# current_source.net
KiCad netlist of a schematic drawn in Altium Designer
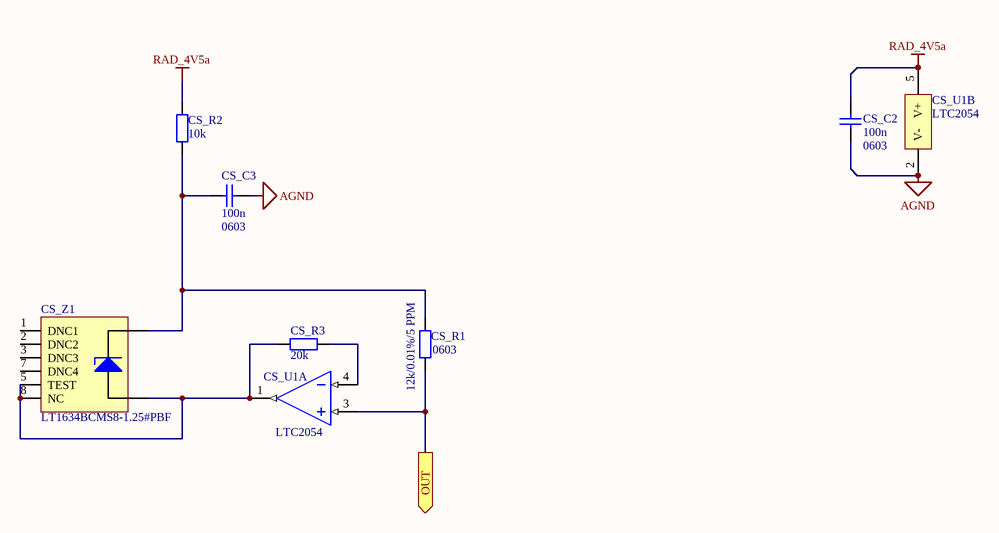
[diagram p0: current_source.SchDoc]

(export (version "E")
  (design (tool "Eeschema 10.0.6"))
  (components
    (comp (ref "CS_C2")
      (value "100n")
      (footprint "SMD_Capacitor_0603")
      (description "Cap")
      (fields (field (name "PACKAGE") "0603"))
      (libsource (lib "capacitors") (part "Cap"))
    )
    (comp (ref "CS_C3")
      (value "100n")
      (footprint "SMD_Capacitor_0603")
      (description "Cap")
      (fields (field (name "PACKAGE") "0603"))
      (libsource (lib "capacitors") (part "Cap"))
    )
    (comp (ref "CS_R1")
      (value "12k/0.01%/5 PPM")
      (footprint "SMD_Resistor_0603")
      (fields (field (name "PACKAGE") "0603"))
      (libsource (lib "") (part "Res_1"))
    )
    (comp (ref "CS_R2") (value "10k") (footprint "SMD_Resistor_0603") (libsource (lib "") (part "Res_1")))
    (comp (ref "CS_R3")
      (value "20k")
      (footprint "SMD_Resistor_0603")
      (libsource (lib "resistors") (part "Res"))
    )
    (comp (ref "CS_U1")
      (value "LTC2054")
      (footprint "SOT23-5")
      (description "Single/Dual Micropower  Zero-Drift Operational Amplifi ers")
      (fields (field (name "MANUFACTURER") "Linear Technology"))
      (libsource (lib "") (part "LTC2054_1"))
    )
    (comp (ref "CS_Z1")
      (value "1.25V")
      (footprint "MSOP-8")
      (description "Micropower Precision  Shunt Voltage Reference")
      (fields
        (field (name "MANUFACTURER") "Linear")
        (field (name "MANUFACTURERPARTNUMBER") "LT1634BCMS8-1.25#PBF")
      )
      (libsource (lib "diodes") (part "LT1634BCMS8-1.25#PBF"))
    )
  )
  (nets
    (net (code "1") (name "/OUT") (class "Default")
      (node (ref "CS_R1") (pin "2") (pinfunction "2_2") (pintype "passive"))
      (node (ref "CS_U1") (pin "3") (pinfunction "IN+_A_3") (pintype "input"))
    )
    (net (code "2") (name "AGND") (class "Default")
      (node (ref "CS_C2") (pin "2") (pinfunction "2_2") (pintype "passive"))
      (node (ref "CS_C3") (pin "1") (pinfunction "1_1") (pintype "passive"))
      (node (ref "CS_U1") (pin "2") (pinfunction "V-_2") (pintype "power_in"))
    )
    (net (code "3") (name "Net-(CS_U1A-IN-_A)") (class "Default")
      (node (ref "CS_R3") (pin "2") (pinfunction "2_2") (pintype "passive"))
      (node (ref "CS_U1") (pin "4") (pinfunction "IN-_A_4") (pintype "input"))
    )
    (net (code "4") (name "Net-(CS_U1A-OUT_A)") (class "Default")
      (node (ref "CS_R3") (pin "1") (pinfunction "1_1") (pintype "passive"))
      (node (ref "CS_U1") (pin "1") (pinfunction "OUT_A_1") (pintype "output"))
      (node (ref "CS_Z1") (pin "4") (pinfunction "A_4") (pintype "passive"))
      (node (ref "CS_Z1") (pin "5") (pinfunction "TEST_5") (pintype "passive"))
      (node (ref "CS_Z1") (pin "8") (pinfunction "NC_8") (pintype "passive"))
    )
    (net (code "5") (name "Net-(CS_Z1-K)") (class "Default")
      (node (ref "CS_C3") (pin "2") (pinfunction "2_2") (pintype "passive"))
      (node (ref "CS_R1") (pin "1") (pinfunction "1_1") (pintype "passive"))
      (node (ref "CS_R2") (pin "2") (pinfunction "2_2") (pintype "passive"))
      (node (ref "CS_Z1") (pin "6") (pinfunction "K_6") (pintype "passive"))
    )
    (net (code "6") (name "RAD_4V5a") (class "Default")
      (node (ref "CS_C2") (pin "1") (pinfunction "1_1") (pintype "passive"))
      (node (ref "CS_R2") (pin "1") (pinfunction "1_1") (pintype "passive"))
      (node (ref "CS_U1") (pin "5") (pinfunction "V+_5") (pintype "power_in"))
    )
    (net (code "7") (name "unconnected-(CS_Z1-DNC1-Pad1)") (class "Default")
      (node (ref "CS_Z1") (pin "1") (pinfunction "DNC1_1") (pintype "passive"))
    )
    (net (code "8") (name "unconnected-(CS_Z1-DNC2-Pad2)") (class "Default")
      (node (ref "CS_Z1") (pin "2") (pinfunction "DNC2_2") (pintype "passive"))
    )
    (net (code "9") (name "unconnected-(CS_Z1-DNC3-Pad3)") (class "Default")
      (node (ref "CS_Z1") (pin "3") (pinfunction "DNC3_3") (pintype "passive"))
    )
    (net (code "10") (name "unconnected-(CS_Z1-DNC4-Pad7)") (class "Default")
      (node (ref "CS_Z1") (pin "7") (pinfunction "DNC4_7") (pintype "passive"))
    )
  )
)
